# RV-3028_Real-Time_Clock.net
KiCad netlist of a schematic drawn in Altium Designer
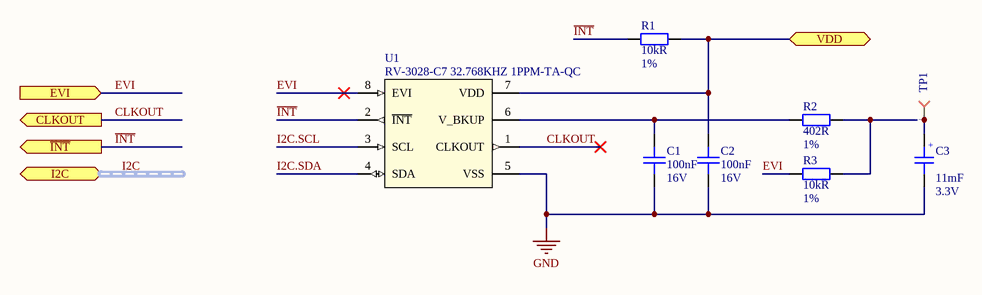
[diagram p0: RV-3028_Real-Time_Clock.SchDoc]

(export (version "E")
  (design (tool "Eeschema 10.0.6"))
  (components
    (comp (ref "C1")
      (value "CAP CER 0.1UF 16V X7R 0402")
      (footprint "C0402")
      (description "0.1µF ±10% 16V Ceramic Capacitor X7R 0402 (1005 Metric)")
      (fields
        (field (name "MANUFACTURER PART NUMBER") "CC0402KRX7R7BB104")
        (field (name "MANUFACTURER") "Yageo")
        (field (name "CAPACITANCE") "100nF")
        (field (name "VOLTAGE") "16V")
      )
      (libsource (lib "capacitors_smd") (part "CAP CER 0.1UF 16V X7R 0402"))
    )
    (comp (ref "C2")
      (value "CAP CER 0.1UF 16V X7R 0402")
      (footprint "C0402")
      (description "0.1µF ±10% 16V Ceramic Capacitor X7R 0402 (1005 Metric)")
      (fields
        (field (name "MANUFACTURER PART NUMBER") "CC0402KRX7R7BB104")
        (field (name "MANUFACTURER") "Yageo")
        (field (name "CAPACITANCE") "100nF")
        (field (name "VOLTAGE") "16V")
      )
      (libsource (lib "capacitors_smd") (part "CAP CER 0.1UF 16V X7R 0402"))
    )
    (comp (ref "C3")
      (value "CAP 11MF 3.3V SURFACE MNT")
      (footprint "CAPCP3225X100N")
      (description "11mF (EDLC) Supercapacitor 3.3V 1210 (3225 Metric)")
      (fields
        (field (name "MANUFACTURER") "Seiko")
        (field (name "MANUFACTURER PART NUMBER") "CPH3225A")
        (field (name "CAPACITANCE") "11mF")
        (field (name "VOLTAGE RATING") "3.3V")
      )
      (libsource (lib "BLDC_Motor_Driver") (part "CAP 11MF 3.3V SURFACE MNT"))
    )
    (comp (ref "R1")
      (value "RES SMD 10K OHM 1% 1/16W 0402")
      (footprint "R0402")
      (description "10 kOhms ±1% 0.063W, 1/16W Chip Resistor 0402 (1005 Metric) Moisture Resistant Thick Film")
      (fields
        (field (name "MANUFACTURER PART NUMBER") "RC0402FR-0710KP")
        (field (name "MANUFACTURER") "Yageo")
        (field (name "RESISTANCE") "10kR")
        (field (name "TOLERANCE") "1%")
      )
      (libsource (lib "resistors_smd") (part "RES SMD 10K OHM 1% 1/16W 0402"))
    )
    (comp (ref "R2")
      (value "RES SMD 402 OHM 1% 1/16W 0402")
      (footprint "R0402")
      (description "402 Ohms ±1% 0.063W, 1/16W Chip Resistor 0402 (1005 Metric) Moisture Resistant Thick Film")
      (fields
        (field (name "MANUFACTURER") "Yageo")
        (field (name "MANUFACTURER PART NUMBER") "RC0402FR-07402RL")
        (field (name "RESISTANCE") "402R")
        (field (name "TOLERANCE") "1%")
      )
      (libsource (lib "resistors_smd") (part "RES SMD 402 OHM 1% 1/16W 0402"))
    )
    (comp (ref "R3")
      (value "RES SMD 10K OHM 1% 1/16W 0402")
      (footprint "R0402")
      (description "10 kOhms ±1% 0.063W, 1/16W Chip Resistor 0402 (1005 Metric) Moisture Resistant Thick Film")
      (fields
        (field (name "MANUFACTURER PART NUMBER") "RC0402FR-0710KP")
        (field (name "MANUFACTURER") "Yageo")
        (field (name "RESISTANCE") "10kR")
        (field (name "TOLERANCE") "1%")
      )
      (libsource (lib "resistors_smd") (part "RES SMD 10K OHM 1% 1/16W 0402"))
    )
    (comp (ref "TP1")
      (value "Test Point Pad")
      (footprint "Testpoint")
      (description "Test Point. There is nothing to buy or mount.")
      (libsource (lib "BLDC_Motor_Driver") (part "Test Point Pad"))
    )
    (comp (ref "U1")
      (value "RV-3028-C7 32.768KHZ 1PPM-TA-QC")
      (footprint "8-SON (3.2x1.5)")
      (description "2-Bit Bidirectional Voltage-Level Translator for Open-Drain Application")
      (fields (field (name "MANUFACTURER") "Micro Crystal"))
      (libsource (lib "BLDC_Motor_Driver") (part "IC RV-3028 RTC CLK/CALENDAR I2C 8-SMT"))
    )
  )
  (nets
    (net (code "2") (name "/CLKOUT") (class "Default")
      (node (ref "U1") (pin "1") (pinfunction "CLKOUT_1") (pintype "output+no_connect"))
    )
    (net (code "3") (name "/EVI") (class "Default")
      (node (ref "R3") (pin "2") (pinfunction "2_2") (pintype "passive"))
      (node (ref "U1") (pin "8") (pinfunction "EVI_8") (pintype "input"))
    )
    (net (code "4") (name "/I2C.SCL") (class "Default")
      (node (ref "U1") (pin "3") (pinfunction "SCL_3") (pintype "input"))
    )
    (net (code "5") (name "/I2C.SDA") (class "Default")
      (node (ref "U1") (pin "4") (pinfunction "SDA_4") (pintype "bidirectional"))
    )
    (net (code "6") (name "/INT") (class "Default")
      (node (ref "R1") (pin "2") (pinfunction "2_2") (pintype "passive"))
      (node (ref "U1") (pin "2") (pinfunction "INT_2") (pintype "output"))
    )
    (net (code "7") (name "/VDD") (class "Default")
      (node (ref "C2") (pin "2") (pinfunction "2_2") (pintype "passive"))
      (node (ref "R1") (pin "1") (pinfunction "1_1") (pintype "passive"))
      (node (ref "U1") (pin "7") (pinfunction "VDD_7") (pintype "power_in"))
    )
    (net (code "9") (name "GND") (class "Default")
      (node (ref "C1") (pin "1") (pinfunction "1_1") (pintype "passive"))
      (node (ref "C2") (pin "1") (pinfunction "1_1") (pintype "passive"))
      (node (ref "C3") (pin "2") (pinfunction "2_2") (pintype "passive"))
      (node (ref "U1") (pin "5") (pinfunction "VSS_5") (pintype "power_in"))
    )
    (net (code "10") (name "Net-(C3-Pad1)") (class "Default")
      (node (ref "C3") (pin "1") (pinfunction "1_1") (pintype "passive"))
      (node (ref "R2") (pin "2") (pinfunction "2_2") (pintype "passive"))
      (node (ref "R3") (pin "1") (pinfunction "1_1") (pintype "passive"))
      (node (ref "TP1") (pin "1") (pinfunction "1_1") (pintype "passive"))
    )
    (net (code "11") (name "Net-(U1-V_BKUP)") (class "Default")
      (node (ref "C1") (pin "2") (pinfunction "2_2") (pintype "passive"))
      (node (ref "R2") (pin "1") (pinfunction "1_1") (pintype "passive"))
      (node (ref "U1") (pin "6") (pinfunction "V_BKUP_6") (pintype "power_in"))
    )
  )
)
